# MusselBedHeater_RevG.net
KiCad netlist of a schematic drawn in EAGLE
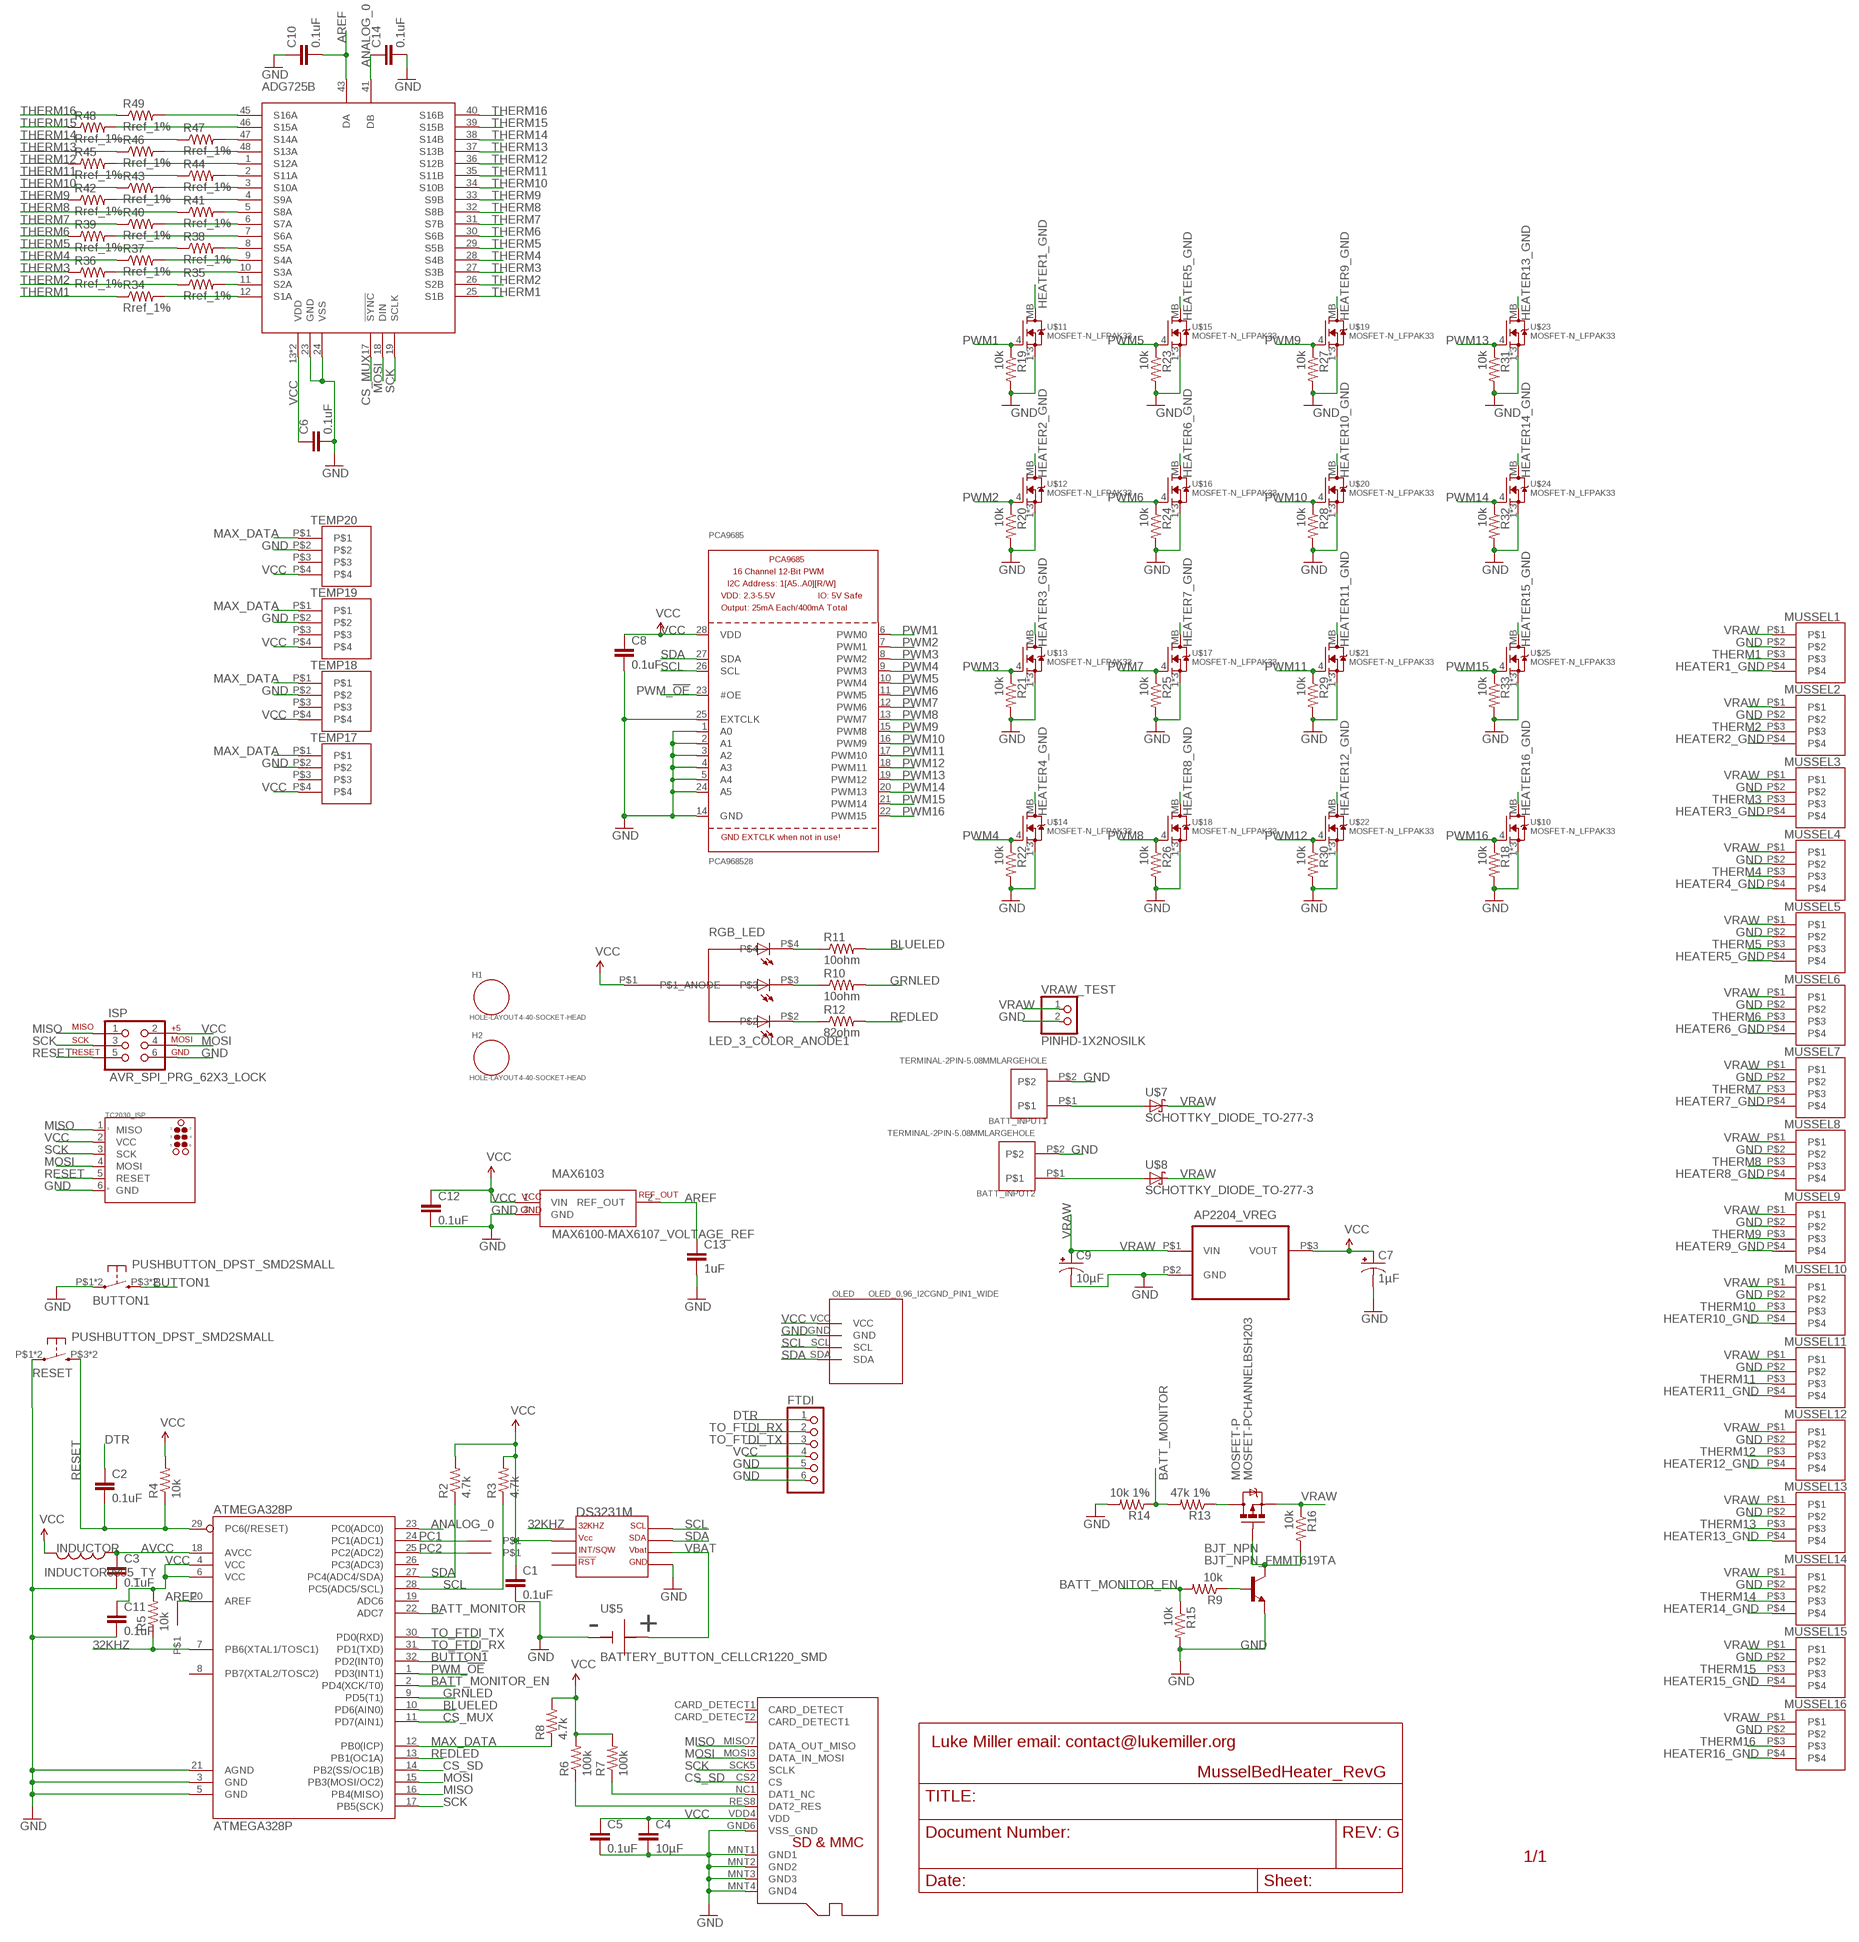
[diagram p0: schematic, sheet 1]

(export (version "E")
  (design (tool "Eeschema 10.0.6"))
  (components
    (comp (ref "ADG725B")
      (value "ADG725_MUX")
      (footprint "eagle-import:TQFP48")
      (libsource (lib "eagle-import") (part "ADG725_MUX"))
    )
    (comp (ref "AP2204_VREG")
      (value "AP2204R")
      (footprint "eagle-import:SOT-89")
      (libsource (lib "eagle-import") (part "AP2204R"))
    )
    (comp (ref "AREF")
      (value "PINHD-1X1STANDARD")
      (footprint "eagle-import:1X01")
      (libsource (lib "eagle-import") (part "PINHD-1X1STANDARD"))
    )
    (comp (ref "ATMEGA328P")
      (value "ATMEGA328P")
      (footprint "eagle-import:TQFP32-08")
      (libsource (lib "eagle-import") (part "ATMEGA328_SMT"))
    )
    (comp (ref "BATT_INPUT1")
      (value "TERMINAL-2PIN-5.08MMLARGEHOLE")
      (footprint "eagle-import:TERMINAL-2PIN-5.08MM_LARGEHOLE")
      (libsource (lib "eagle-import") (part "TERMINAL-2PIN-5.08MMLARGEHOLE"))
    )
    (comp (ref "BATT_INPUT2")
      (value "TERMINAL-2PIN-5.08MMLARGEHOLE")
      (footprint "eagle-import:TERMINAL-2PIN-5.08MM_LARGEHOLE")
      (libsource (lib "eagle-import") (part "TERMINAL-2PIN-5.08MMLARGEHOLE"))
    )
    (comp (ref "BJT_NPN")
      (value "BJT_NPN_FMMT619TA")
      (footprint "eagle-import:SOT23")
      (libsource (lib "eagle-import") (part "BJT_NPN_FMMT619TA"))
    )
    (comp (ref "BUTTON1")
      (value "PUSHBUTTON_DPST_SMD2SMALL")
      (footprint "eagle-import:PUSHBUTTON_SPST_PTS525_SERIES")
      (libsource (lib "eagle-import") (part "PUSHBUTTON_DPST_SMD2SMALL"))
    )
    (comp (ref "C1")
      (value "0.1uF")
      (footprint "eagle-import:0603")
      (libsource (lib "eagle-import") (part "CAP0603"))
    )
    (comp (ref "C2")
      (value "0.1uF")
      (footprint "eagle-import:0603")
      (libsource (lib "eagle-import") (part "CAP0603"))
    )
    (comp (ref "C3")
      (value "0.1uF")
      (footprint "eagle-import:0603")
      (libsource (lib "eagle-import") (part "CAP0603"))
    )
    (comp (ref "C4")
      (value "10µF")
      (footprint "eagle-import:0603")
      (libsource (lib "eagle-import") (part "CAP0603"))
    )
    (comp (ref "C5")
      (value "0.1uF")
      (footprint "eagle-import:0603")
      (libsource (lib "eagle-import") (part "CAP0603"))
    )
    (comp (ref "C6")
      (value "0.1uF")
      (footprint "eagle-import:0603")
      (libsource (lib "eagle-import") (part "CAP0603"))
    )
    (comp (ref "C7")
      (value "1µF")
      (footprint "eagle-import:PANASONIC_B")
      (libsource (lib "eagle-import") (part "CPOL-USB"))
    )
    (comp (ref "C8")
      (value "0.1uF")
      (footprint "eagle-import:0603")
      (libsource (lib "eagle-import") (part "CAP0603"))
    )
    (comp (ref "C9")
      (value "10µF")
      (footprint "eagle-import:PANASONIC_C")
      (libsource (lib "eagle-import") (part "CPOL-USC"))
    )
    (comp (ref "C10")
      (value "0.1uF")
      (footprint "eagle-import:0603")
      (libsource (lib "eagle-import") (part "CAP0603"))
    )
    (comp (ref "C11")
      (value "0.1uF")
      (footprint "eagle-import:0603")
      (libsource (lib "eagle-import") (part "CAP0603"))
    )
    (comp (ref "C12")
      (value "0.1uF")
      (footprint "eagle-import:0603")
      (libsource (lib "eagle-import") (part "CAP0603"))
    )
    (comp (ref "C13")
      (value "1uF")
      (footprint "eagle-import:0603")
      (libsource (lib "eagle-import") (part "CAP0603"))
    )
    (comp (ref "C14")
      (value "0.1uF")
      (footprint "eagle-import:0603")
      (libsource (lib "eagle-import") (part "CAP0603"))
    )
    (comp (ref "DS3231M")
      (value "DS3231MSOIC-8")
      (footprint "eagle-import:DS3231M_SOIC8")
      (libsource (lib "eagle-import") (part "DS3231MSOIC-8"))
    )
    (comp (ref "FTDI")
      (value "PINHD-1X6RA")
      (footprint "eagle-import:1X06-RIGHT_ANGLE")
      (libsource (lib "eagle-import") (part "PINHD-1X6RA"))
    )
    (comp (ref "H1")
      (value "HOLE-LAYOUT4-40-SOCKET-HEAD")
      (footprint "eagle-import:4-40-SCREW-HOLE")
      (libsource (lib "eagle-import") (part "HOLE-LAYOUT4-40-SOCKET-HEAD"))
    )
    (comp (ref "H2")
      (value "HOLE-LAYOUT4-40-SOCKET-HEAD")
      (footprint "eagle-import:4-40-SCREW-HOLE")
      (libsource (lib "eagle-import") (part "HOLE-LAYOUT4-40-SOCKET-HEAD"))
    )
    (comp (ref "INDUCTOR")
      (value "INDUCTOR0805_TY")
      (footprint "eagle-import:I_0805")
      (libsource (lib "eagle-import") (part "INDUCTOR0805_TY"))
    )
    (comp (ref "ISP")
      (value "AVR_SPI_PRG_62X3_LOCK")
      (footprint "eagle-import:2X3_LOCK")
      (libsource (lib "eagle-import") (part "AVR_SPI_PRG_62X3_LOCK"))
    )
    (comp (ref "MAX6103")
      (value "MAX6100-MAX6107_VOLTAGE_REF")
      (footprint "eagle-import:SOT23-3")
      (libsource (lib "eagle-import") (part "MAX6100-MAX6107_VOLTAGE_REF"))
    )
    (comp (ref "MOSFET-P")
      (value "MOSFET-PCHANNELBSH203")
      (footprint "eagle-import:SOT23-3")
      (libsource (lib "eagle-import") (part "MOSFET-PCHANNELBSH203"))
    )
    (comp (ref "MUSSEL1")
      (value "MOLEX_KK_254_4_PIN_HEADER")
      (footprint "eagle-import:MOLEX_KK_254_4PIN_HEADER")
      (libsource (lib "eagle-import") (part "MOLEX_KK_254_4_PIN_HEADER"))
    )
    (comp (ref "MUSSEL2")
      (value "MOLEX_KK_254_4_PIN_HEADER")
      (footprint "eagle-import:MOLEX_KK_254_4PIN_HEADER")
      (libsource (lib "eagle-import") (part "MOLEX_KK_254_4_PIN_HEADER"))
    )
    (comp (ref "MUSSEL3")
      (value "MOLEX_KK_254_4_PIN_HEADER")
      (footprint "eagle-import:MOLEX_KK_254_4PIN_HEADER")
      (libsource (lib "eagle-import") (part "MOLEX_KK_254_4_PIN_HEADER"))
    )
    (comp (ref "MUSSEL4")
      (value "MOLEX_KK_254_4_PIN_HEADER")
      (footprint "eagle-import:MOLEX_KK_254_4PIN_HEADER")
      (libsource (lib "eagle-import") (part "MOLEX_KK_254_4_PIN_HEADER"))
    )
    (comp (ref "MUSSEL5")
      (value "MOLEX_KK_254_4_PIN_HEADER")
      (footprint "eagle-import:MOLEX_KK_254_4PIN_HEADER")
      (libsource (lib "eagle-import") (part "MOLEX_KK_254_4_PIN_HEADER"))
    )
    (comp (ref "MUSSEL6")
      (value "MOLEX_KK_254_4_PIN_HEADER")
      (footprint "eagle-import:MOLEX_KK_254_4PIN_HEADER")
      (libsource (lib "eagle-import") (part "MOLEX_KK_254_4_PIN_HEADER"))
    )
    (comp (ref "MUSSEL7")
      (value "MOLEX_KK_254_4_PIN_HEADER")
      (footprint "eagle-import:MOLEX_KK_254_4PIN_HEADER")
      (libsource (lib "eagle-import") (part "MOLEX_KK_254_4_PIN_HEADER"))
    )
    (comp (ref "MUSSEL8")
      (value "MOLEX_KK_254_4_PIN_HEADER")
      (footprint "eagle-import:MOLEX_KK_254_4PIN_HEADER")
      (libsource (lib "eagle-import") (part "MOLEX_KK_254_4_PIN_HEADER"))
    )
    (comp (ref "MUSSEL9")
      (value "MOLEX_KK_254_4_PIN_HEADER")
      (footprint "eagle-import:MOLEX_KK_254_4PIN_HEADER")
      (libsource (lib "eagle-import") (part "MOLEX_KK_254_4_PIN_HEADER"))
    )
    (comp (ref "MUSSEL10")
      (value "MOLEX_KK_254_4_PIN_HEADER")
      (footprint "eagle-import:MOLEX_KK_254_4PIN_HEADER")
      (libsource (lib "eagle-import") (part "MOLEX_KK_254_4_PIN_HEADER"))
    )
    (comp (ref "MUSSEL11")
      (value "MOLEX_KK_254_4_PIN_HEADER")
      (footprint "eagle-import:MOLEX_KK_254_4PIN_HEADER")
      (libsource (lib "eagle-import") (part "MOLEX_KK_254_4_PIN_HEADER"))
    )
    (comp (ref "MUSSEL12")
      (value "MOLEX_KK_254_4_PIN_HEADER")
      (footprint "eagle-import:MOLEX_KK_254_4PIN_HEADER")
      (libsource (lib "eagle-import") (part "MOLEX_KK_254_4_PIN_HEADER"))
    )
    (comp (ref "MUSSEL13")
      (value "MOLEX_KK_254_4_PIN_HEADER")
      (footprint "eagle-import:MOLEX_KK_254_4PIN_HEADER")
      (libsource (lib "eagle-import") (part "MOLEX_KK_254_4_PIN_HEADER"))
    )
    (comp (ref "MUSSEL14")
      (value "MOLEX_KK_254_4_PIN_HEADER")
      (footprint "eagle-import:MOLEX_KK_254_4PIN_HEADER")
      (libsource (lib "eagle-import") (part "MOLEX_KK_254_4_PIN_HEADER"))
    )
    (comp (ref "MUSSEL15")
      (value "MOLEX_KK_254_4_PIN_HEADER")
      (footprint "eagle-import:MOLEX_KK_254_4PIN_HEADER")
      (libsource (lib "eagle-import") (part "MOLEX_KK_254_4_PIN_HEADER"))
    )
    (comp (ref "MUSSEL16")
      (value "MOLEX_KK_254_4_PIN_HEADER")
      (footprint "eagle-import:MOLEX_KK_254_4PIN_HEADER")
      (libsource (lib "eagle-import") (part "MOLEX_KK_254_4_PIN_HEADER"))
    )
    (comp (ref "OLED")
      (value "OLED_0.96_I2CGND_PIN1_WIDE")
      (footprint "eagle-import:OLED_0.96_I2C_GND_PIN1_WIDE")
      (libsource (lib "eagle-import") (part "OLED_0.96_I2CGND_PIN1_WIDE"))
    )
    (comp (ref "PC1")
      (value "PINHD-1X1STANDARD")
      (footprint "eagle-import:1X01")
      (libsource (lib "eagle-import") (part "PINHD-1X1STANDARD"))
    )
    (comp (ref "PC2")
      (value "PINHD-1X1STANDARD")
      (footprint "eagle-import:1X01")
      (libsource (lib "eagle-import") (part "PINHD-1X1STANDARD"))
    )
    (comp (ref "PCA9685")
      (value "PCA968528")
      (footprint "eagle-import:28-TSSOP")
      (libsource (lib "eagle-import") (part "PCA968528"))
    )
    (comp (ref "R2")
      (value "4.7k")
      (footprint "eagle-import:R0603")
      (libsource (lib "eagle-import") (part "RESISTOR_SMDR0603"))
    )
    (comp (ref "R3")
      (value "4.7k")
      (footprint "eagle-import:R0603")
      (libsource (lib "eagle-import") (part "RESISTOR_SMDR0603"))
    )
    (comp (ref "R4")
      (value "10k")
      (footprint "eagle-import:R0603")
      (libsource (lib "eagle-import") (part "RESISTOR_SMDR0603"))
    )
    (comp (ref "R5")
      (value "10k")
      (footprint "eagle-import:R0603")
      (libsource (lib "eagle-import") (part "RESISTOR_SMDR0603"))
    )
    (comp (ref "R6")
      (value "100k")
      (footprint "eagle-import:R0603")
      (libsource (lib "eagle-import") (part "RESISTOR_SMDR0603"))
    )
    (comp (ref "R7")
      (value "100k")
      (footprint "eagle-import:R0603")
      (libsource (lib "eagle-import") (part "RESISTOR_SMDR0603"))
    )
    (comp (ref "R8")
      (value "4.7k")
      (footprint "eagle-import:R0603")
      (libsource (lib "eagle-import") (part "RESISTOR_SMDR0603"))
    )
    (comp (ref "R9")
      (value "10k")
      (footprint "eagle-import:R0603")
      (libsource (lib "eagle-import") (part "RESISTOR_SMDR0603"))
    )
    (comp (ref "R10")
      (value "10ohm")
      (footprint "eagle-import:R0603")
      (libsource (lib "eagle-import") (part "RESISTOR_SMDR0603"))
    )
    (comp (ref "R11")
      (value "10ohm")
      (footprint "eagle-import:R0603")
      (libsource (lib "eagle-import") (part "RESISTOR_SMDR0603"))
    )
    (comp (ref "R12")
      (value "82ohm")
      (footprint "eagle-import:R0603")
      (libsource (lib "eagle-import") (part "RESISTOR_SMDR0603"))
    )
    (comp (ref "R13")
      (value "47k 1%")
      (footprint "eagle-import:R0603")
      (libsource (lib "eagle-import") (part "RESISTOR_SMDR0603"))
    )
    (comp (ref "R14")
      (value "10k 1%")
      (footprint "eagle-import:R0603")
      (libsource (lib "eagle-import") (part "RESISTOR_SMDR0603"))
    )
    (comp (ref "R15")
      (value "10k")
      (footprint "eagle-import:R0603")
      (libsource (lib "eagle-import") (part "RESISTOR_SMDR0603"))
    )
    (comp (ref "R16")
      (value "10k")
      (footprint "eagle-import:R0603")
      (libsource (lib "eagle-import") (part "RESISTOR_SMDR0603"))
    )
    (comp (ref "R18")
      (value "10k")
      (footprint "eagle-import:R0603")
      (libsource (lib "eagle-import") (part "RESISTOR_SMDR0603"))
    )
    (comp (ref "R19")
      (value "10k")
      (footprint "eagle-import:R0603")
      (libsource (lib "eagle-import") (part "RESISTOR_SMDR0603"))
    )
    (comp (ref "R20")
      (value "10k")
      (footprint "eagle-import:R0603")
      (libsource (lib "eagle-import") (part "RESISTOR_SMDR0603"))
    )
    (comp (ref "R21")
      (value "10k")
      (footprint "eagle-import:R0603")
      (libsource (lib "eagle-import") (part "RESISTOR_SMDR0603"))
    )
    (comp (ref "R22")
      (value "10k")
      (footprint "eagle-import:R0603")
      (libsource (lib "eagle-import") (part "RESISTOR_SMDR0603"))
    )
    (comp (ref "R23")
      (value "10k")
      (footprint "eagle-import:R0603")
      (libsource (lib "eagle-import") (part "RESISTOR_SMDR0603"))
    )
    (comp (ref "R24")
      (value "10k")
      (footprint "eagle-import:R0603")
      (libsource (lib "eagle-import") (part "RESISTOR_SMDR0603"))
    )
    (comp (ref "R25")
      (value "10k")
      (footprint "eagle-import:R0603")
      (libsource (lib "eagle-import") (part "RESISTOR_SMDR0603"))
    )
    (comp (ref "R26")
      (value "10k")
      (footprint "eagle-import:R0603")
      (libsource (lib "eagle-import") (part "RESISTOR_SMDR0603"))
    )
    (comp (ref "R27")
      (value "10k")
      (footprint "eagle-import:R0603")
      (libsource (lib "eagle-import") (part "RESISTOR_SMDR0603"))
    )
    (comp (ref "R28")
      (value "10k")
      (footprint "eagle-import:R0603")
      (libsource (lib "eagle-import") (part "RESISTOR_SMDR0603"))
    )
    (comp (ref "R29")
      (value "10k")
      (footprint "eagle-import:R0603")
      (libsource (lib "eagle-import") (part "RESISTOR_SMDR0603"))
    )
    (comp (ref "R30")
      (value "10k")
      (footprint "eagle-import:R0603")
      (libsource (lib "eagle-import") (part "RESISTOR_SMDR0603"))
    )
    (comp (ref "R31")
      (value "10k")
      (footprint "eagle-import:R0603")
      (libsource (lib "eagle-import") (part "RESISTOR_SMDR0603"))
    )
    (comp (ref "R32")
      (value "10k")
      (footprint "eagle-import:R0603")
      (libsource (lib "eagle-import") (part "RESISTOR_SMDR0603"))
    )
    (comp (ref "R33")
      (value "10k")
      (footprint "eagle-import:R0603")
      (libsource (lib "eagle-import") (part "RESISTOR_SMDR0603"))
    )
    (comp (ref "R34")
      (value "Rref_1%")
      (footprint "eagle-import:R0603")
      (libsource (lib "eagle-import") (part "RESISTOR_SMDR0603"))
    )
    (comp (ref "R35")
      (value "Rref_1%")
      (footprint "eagle-import:R0603")
      (libsource (lib "eagle-import") (part "RESISTOR_SMDR0603"))
    )
    (comp (ref "R36")
      (value "Rref_1%")
      (footprint "eagle-import:R0603")
      (libsource (lib "eagle-import") (part "RESISTOR_SMDR0603"))
    )
    (comp (ref "R37")
      (value "Rref_1%")
      (footprint "eagle-import:R0603")
      (libsource (lib "eagle-import") (part "RESISTOR_SMDR0603"))
    )
    (comp (ref "R38")
      (value "Rref_1%")
      (footprint "eagle-import:R0603")
      (libsource (lib "eagle-import") (part "RESISTOR_SMDR0603"))
    )
    (comp (ref "R39")
      (value "Rref_1%")
      (footprint "eagle-import:R0603")
      (libsource (lib "eagle-import") (part "RESISTOR_SMDR0603"))
    )
    (comp (ref "R40")
      (value "Rref_1%")
      (footprint "eagle-import:R0603")
      (libsource (lib "eagle-import") (part "RESISTOR_SMDR0603"))
    )
    (comp (ref "R41")
      (value "Rref_1%")
      (footprint "eagle-import:R0603")
      (libsource (lib "eagle-import") (part "RESISTOR_SMDR0603"))
    )
    (comp (ref "R42")
      (value "Rref_1%")
      (footprint "eagle-import:R0603")
      (libsource (lib "eagle-import") (part "RESISTOR_SMDR0603"))
    )
    (comp (ref "R43")
      (value "Rref_1%")
      (footprint "eagle-import:R0603")
      (libsource (lib "eagle-import") (part "RESISTOR_SMDR0603"))
    )
    (comp (ref "R44")
      (value "Rref_1%")
      (footprint "eagle-import:R0603")
      (libsource (lib "eagle-import") (part "RESISTOR_SMDR0603"))
    )
    (comp (ref "R45")
      (value "Rref_1%")
      (footprint "eagle-import:R0603")
      (libsource (lib "eagle-import") (part "RESISTOR_SMDR0603"))
    )
    (comp (ref "R46")
      (value "Rref_1%")
      (footprint "eagle-import:R0603")
      (libsource (lib "eagle-import") (part "RESISTOR_SMDR0603"))
    )
    (comp (ref "R47")
      (value "Rref_1%")
      (footprint "eagle-import:R0603")
      (libsource (lib "eagle-import") (part "RESISTOR_SMDR0603"))
    )
    (comp (ref "R48")
      (value "Rref_1%")
      (footprint "eagle-import:R0603")
      (libsource (lib "eagle-import") (part "RESISTOR_SMDR0603"))
    )
    (comp (ref "R49")
      (value "Rref_1%")
      (footprint "eagle-import:R0603")
      (libsource (lib "eagle-import") (part "RESISTOR_SMDR0603"))
    )
    (comp (ref "RESET")
      (value "PUSHBUTTON_DPST_SMD2SMALL")
      (footprint "eagle-import:PUSHBUTTON_SPST_PTS525_SERIES")
      (libsource (lib "eagle-import") (part "PUSHBUTTON_DPST_SMD2SMALL"))
    )
    (comp (ref "RGB_LED")
      (value "LED_3_COLOR_ANODE1")
      (footprint "eagle-import:LED_RGB_SMD_1.6X1.6")
      (libsource (lib "eagle-import") (part "LED_3_COLOR_ANODE1"))
    )
    (comp (ref "TC2030_ISP")
      (value "TC2030-MCP-NL")
      (footprint "eagle-import:TC2030-MCP-NL")
      (libsource (lib "eagle-import") (part "TC2030-MCP-NL"))
    )
    (comp (ref "TEMP17")
      (value "MOLEX_KK_254_4_PIN_HEADER")
      (footprint "eagle-import:MOLEX_KK_254_4PIN_HEADER")
      (libsource (lib "eagle-import") (part "MOLEX_KK_254_4_PIN_HEADER"))
    )
    (comp (ref "TEMP18")
      (value "MOLEX_KK_254_4_PIN_HEADER")
      (footprint "eagle-import:MOLEX_KK_254_4PIN_HEADER")
      (libsource (lib "eagle-import") (part "MOLEX_KK_254_4_PIN_HEADER"))
    )
    (comp (ref "TEMP19")
      (value "MOLEX_KK_254_4_PIN_HEADER")
      (footprint "eagle-import:MOLEX_KK_254_4PIN_HEADER")
      (libsource (lib "eagle-import") (part "MOLEX_KK_254_4_PIN_HEADER"))
    )
    (comp (ref "TEMP20")
      (value "MOLEX_KK_254_4_PIN_HEADER")
      (footprint "eagle-import:MOLEX_KK_254_4PIN_HEADER")
      (libsource (lib "eagle-import") (part "MOLEX_KK_254_4_PIN_HEADER"))
    )
    (comp (ref "U$2")
      (value "MICROSD_MOLEX_REVERSECURRENT")
      (footprint "eagle-import:MICROSD_SOCKET_MOLEX_REVERSEMOUNT")
      (libsource (lib "eagle-import") (part "MICROSD_MOLEX_REVERSECURRENT"))
    )
    (comp (ref "U$5")
      (value "BATTERY_BUTTON_CELLCR1220_SMD")
      (footprint "eagle-import:CR1220_BATTERY_HOLDER_SMD")
      (libsource (lib "eagle-import") (part "BATTERY_BUTTON_CELLCR1220_SMD"))
    )
    (comp (ref "U$7")
      (value "SCHOTTKY_DIODE_TO-277-3")
      (footprint "eagle-import:TO-277-3")
      (libsource (lib "eagle-import") (part "SCHOTTKY_DIODE_TO-277-3"))
    )
    (comp (ref "U$8")
      (value "SCHOTTKY_DIODE_TO-277-3")
      (footprint "eagle-import:TO-277-3")
      (libsource (lib "eagle-import") (part "SCHOTTKY_DIODE_TO-277-3"))
    )
    (comp (ref "U$10")
      (value "MOSFET-N_LFPAK33")
      (footprint "eagle-import:SOT1210")
      (libsource (lib "eagle-import") (part "MOSFET-N_LFPAK33"))
    )
    (comp (ref "U$11")
      (value "MOSFET-N_LFPAK33")
      (footprint "eagle-import:SOT1210")
      (libsource (lib "eagle-import") (part "MOSFET-N_LFPAK33"))
    )
    (comp (ref "U$12")
      (value "MOSFET-N_LFPAK33")
      (footprint "eagle-import:SOT1210")
      (libsource (lib "eagle-import") (part "MOSFET-N_LFPAK33"))
    )
    (comp (ref "U$13")
      (value "MOSFET-N_LFPAK33")
      (footprint "eagle-import:SOT1210")
      (libsource (lib "eagle-import") (part "MOSFET-N_LFPAK33"))
    )
    (comp (ref "U$14")
      (value "MOSFET-N_LFPAK33")
      (footprint "eagle-import:SOT1210")
      (libsource (lib "eagle-import") (part "MOSFET-N_LFPAK33"))
    )
    (comp (ref "U$15")
      (value "MOSFET-N_LFPAK33")
      (footprint "eagle-import:SOT1210")
      (libsource (lib "eagle-import") (part "MOSFET-N_LFPAK33"))
    )
    (comp (ref "U$16")
      (value "MOSFET-N_LFPAK33")
      (footprint "eagle-import:SOT1210")
      (libsource (lib "eagle-import") (part "MOSFET-N_LFPAK33"))
    )
    (comp (ref "U$17")
      (value "MOSFET-N_LFPAK33")
      (footprint "eagle-import:SOT1210")
      (libsource (lib "eagle-import") (part "MOSFET-N_LFPAK33"))
    )
    (comp (ref "U$18")
      (value "MOSFET-N_LFPAK33")
      (footprint "eagle-import:SOT1210")
      (libsource (lib "eagle-import") (part "MOSFET-N_LFPAK33"))
    )
    (comp (ref "U$19")
      (value "MOSFET-N_LFPAK33")
      (footprint "eagle-import:SOT1210")
      (libsource (lib "eagle-import") (part "MOSFET-N_LFPAK33"))
    )
    (comp (ref "U$20")
      (value "MOSFET-N_LFPAK33")
      (footprint "eagle-import:SOT1210")
      (libsource (lib "eagle-import") (part "MOSFET-N_LFPAK33"))
    )
    (comp (ref "U$21")
      (value "MOSFET-N_LFPAK33")
      (footprint "eagle-import:SOT1210")
      (libsource (lib "eagle-import") (part "MOSFET-N_LFPAK33"))
    )
    (comp (ref "U$22")
      (value "MOSFET-N_LFPAK33")
      (footprint "eagle-import:SOT1210")
      (libsource (lib "eagle-import") (part "MOSFET-N_LFPAK33"))
    )
    (comp (ref "U$23")
      (value "MOSFET-N_LFPAK33")
      (footprint "eagle-import:SOT1210")
      (libsource (lib "eagle-import") (part "MOSFET-N_LFPAK33"))
    )
    (comp (ref "U$24")
      (value "MOSFET-N_LFPAK33")
      (footprint "eagle-import:SOT1210")
      (libsource (lib "eagle-import") (part "MOSFET-N_LFPAK33"))
    )
    (comp (ref "U$25")
      (value "MOSFET-N_LFPAK33")
      (footprint "eagle-import:SOT1210")
      (libsource (lib "eagle-import") (part "MOSFET-N_LFPAK33"))
    )
    (comp (ref "VRAW_TEST")
      (value "PINHD-1X2NOSILK")
      (footprint "eagle-import:1X02_NOSILK")
      (libsource (lib "eagle-import") (part "PINHD-1X2NOSILK"))
    )
  )
  (nets
    (net (code "1") (name "/32KHZ") (class "Default")
      (node (ref "ATMEGA328P") (pin "7") (pinfunction "PB6(XTAL1/TOSC1)_7") (pintype "bidirectional"))
      (node (ref "DS3231M") (pin "1") (pinfunction "P$1_32KHZ_1") (pintype "bidirectional"))
      (node (ref "R5") (pin "1") (pinfunction "1_1") (pintype "passive"))
    )
    (net (code "2") (name "/ANALOG_0") (class "Default")
      (node (ref "ADG725B") (pin "41") (pinfunction "DB_41") (pintype "bidirectional"))
      (node (ref "ATMEGA328P") (pin "23") (pinfunction "PC0(ADC0)_23") (pintype "bidirectional"))
      (node (ref "C14") (pin "1") (pinfunction "1_1") (pintype "passive"))
    )
    (net (code "3") (name "/AREF") (class "Default")
      (node (ref "ADG725B") (pin "43") (pinfunction "DA_43") (pintype "bidirectional"))
      (node (ref "AREF") (pin "1") (pinfunction "P$1_1") (pintype "bidirectional"))
      (node (ref "ATMEGA328P") (pin "20") (pinfunction "AREF_20") (pintype "bidirectional"))
      (node (ref "C10") (pin "2") (pinfunction "2_2") (pintype "passive"))
      (node (ref "C13") (pin "1") (pinfunction "1_1") (pintype "passive"))
      (node (ref "MAX6103") (pin "2") (pinfunction "REF_OUT_2") (pintype "bidirectional"))
    )
    (net (code "4") (name "/AVCC") (class "Default")
      (node (ref "ATMEGA328P") (pin "18") (pinfunction "AVCC_18") (pintype "bidirectional"))
      (node (ref "C3") (pin "1") (pinfunction "1_1") (pintype "passive"))
      (node (ref "INDUCTOR") (pin "P$1") (pinfunction "1_P$1") (pintype "passive"))
    )
    (net (code "5") (name "/BATT_MONITOR") (class "Default")
      (node (ref "ATMEGA328P") (pin "22") (pinfunction "ADC7_22") (pintype "bidirectional"))
      (node (ref "R13") (pin "2") (pinfunction "2_2") (pintype "passive"))
      (node (ref "R14") (pin "1") (pinfunction "1_1") (pintype "passive"))
    )
    (net (code "6") (name "/BATT_MONITOR_EN") (class "Default")
      (node (ref "ATMEGA328P") (pin "2") (pinfunction "PD4(XCK/T0)_2") (pintype "bidirectional"))
      (node (ref "R15") (pin "1") (pinfunction "1_1") (pintype "passive"))
      (node (ref "R9") (pin "2") (pinfunction "2_2") (pintype "passive"))
    )
    (net (code "7") (name "/BLUELED") (class "Default")
      (node (ref "ATMEGA328P") (pin "10") (pinfunction "PD6(AIN0)_10") (pintype "bidirectional"))
      (node (ref "R11") (pin "2") (pinfunction "2_2") (pintype "passive"))
    )
    (net (code "8") (name "/BUTTON1") (class "Default")
      (node (ref "ATMEGA328P") (pin "32") (pinfunction "PD2(INT0)_32") (pintype "bidirectional"))
      (node (ref "BUTTON1") (pin "P$3") (pinfunction "S_P$3") (pintype "passive"))
      (node (ref "BUTTON1") (pin "P$4") (pinfunction "S_P$4") (pintype "passive"))
    )
    (net (code "9") (name "/CS_MUX") (class "Default")
      (node (ref "ADG725B") (pin "17") (pinfunction "~{SYNC}_17") (pintype "bidirectional"))
      (node (ref "ATMEGA328P") (pin "11") (pinfunction "PD7(AIN1)_11") (pintype "bidirectional"))
    )
    (net (code "10") (name "/CS_SD") (class "Default")
      (node (ref "ATMEGA328P") (pin "14") (pinfunction "PB2(SS/OC1B)_14") (pintype "bidirectional"))
      (node (ref "U$2") (pin "CS2") (pinfunction "CS_CS2") (pintype "input"))
    )
    (net (code "11") (name "/DTR") (class "Default")
      (node (ref "C2") (pin "1") (pinfunction "1_1") (pintype "passive"))
      (node (ref "FTDI") (pin "1") (pinfunction "1_1") (pintype "passive"))
    )
    (net (code "12") (name "/GRNLED") (class "Default")
      (node (ref "ATMEGA328P") (pin "9") (pinfunction "PD5(T1)_9") (pintype "bidirectional"))
      (node (ref "R10") (pin "2") (pinfunction "2_2") (pintype "passive"))
    )
    (net (code "13") (name "/HEATER1_GND") (class "Default")
      (node (ref "MUSSEL1") (pin "P$4") (pinfunction "P$4_P$4") (pintype "bidirectional"))
      (node (ref "U$11") (pin "MB") (pinfunction "D_MB") (pintype "bidirectional"))
    )
    (net (code "14") (name "/HEATER2_GND") (class "Default")
      (node (ref "MUSSEL2") (pin "P$4") (pinfunction "P$4_P$4") (pintype "bidirectional"))
      (node (ref "U$12") (pin "MB") (pinfunction "D_MB") (pintype "bidirectional"))
    )
    (net (code "15") (name "/HEATER3_GND") (class "Default")
      (node (ref "MUSSEL3") (pin "P$4") (pinfunction "P$4_P$4") (pintype "bidirectional"))
      (node (ref "U$13") (pin "MB") (pinfunction "D_MB") (pintype "bidirectional"))
    )
    (net (code "16") (name "/HEATER4_GND") (class "Default")
      (node (ref "MUSSEL4") (pin "P$4") (pinfunction "P$4_P$4") (pintype "bidirectional"))
      (node (ref "U$14") (pin "MB") (pinfunction "D_MB") (pintype "bidirectional"))
    )
    (net (code "17") (name "/HEATER5_GND") (class "Default")
      (node (ref "MUSSEL5") (pin "P$4") (pinfunction "P$4_P$4") (pintype "bidirectional"))
      (node (ref "U$15") (pin "MB") (pinfunction "D_MB") (pintype "bidirectional"))
    )
    (net (code "18") (name "/HEATER6_GND") (class "Default")
      (node (ref "MUSSEL6") (pin "P$4") (pinfunction "P$4_P$4") (pintype "bidirectional"))
      (node (ref "U$16") (pin "MB") (pinfunction "D_MB") (pintype "bidirectional"))
    )
    (net (code "19") (name "/HEATER7_GND") (class "Default")
      (node (ref "MUSSEL7") (pin "P$4") (pinfunction "P$4_P$4") (pintype "bidirectional"))
      (node (ref "U$17") (pin "MB") (pinfunction "D_MB") (pintype "bidirectional"))
    )
    (net (code "20") (name "/HEATER8_GND") (class "Default")
      (node (ref "MUSSEL8") (pin "P$4") (pinfunction "P$4_P$4") (pintype "bidirectional"))
      (node (ref "U$18") (pin "MB") (pinfunction "D_MB") (pintype "bidirectional"))
    )
    (net (code "21") (name "/HEATER9_GND") (class "Default")
      (node (ref "MUSSEL9") (pin "P$4") (pinfunction "P$4_P$4") (pintype "bidirectional"))
      (node (ref "U$19") (pin "MB") (pinfunction "D_MB") (pintype "bidirectional"))
    )
    (net (code "22") (name "/HEATER10_GND") (class "Default")
      (node (ref "MUSSEL10") (pin "P$4") (pinfunction "P$4_P$4") (pintype "bidirectional"))
      (node (ref "U$20") (pin "MB") (pinfunction "D_MB") (pintype "bidirectional"))
    )
    (net (code "23") (name "/HEATER11_GND") (class "Default")
      (node (ref "MUSSEL11") (pin "P$4") (pinfunction "P$4_P$4") (pintype "bidirectional"))
      (node (ref "U$21") (pin "MB") (pinfunction "D_MB") (pintype "bidirectional"))
    )
    (net (code "24") (name "/HEATER12_GND") (class "Default")
      (node (ref "MUSSEL12") (pin "P$4") (pinfunction "P$4_P$4") (pintype "bidirectional"))
      (node (ref "U$22") (pin "MB") (pinfunction "D_MB") (pintype "bidirectional"))
    )
    (net (code "25") (name "/HEATER13_GND") (class "Default")
      (node (ref "MUSSEL13") (pin "P$4") (pinfunction "P$4_P$4") (pintype "bidirectional"))
      (node (ref "U$23") (pin "MB") (pinfunction "D_MB") (pintype "bidirectional"))
    )
    (net (code "26") (name "/HEATER14_GND") (class "Default")
      (node (ref "MUSSEL14") (pin "P$4") (pinfunction "P$4_P$4") (pintype "bidirectional"))
      (node (ref "U$24") (pin "MB") (pinfunction "D_MB") (pintype "bidirectional"))
    )
    (net (code "27") (name "/HEATER15_GND") (class "Default")
      (node (ref "MUSSEL15") (pin "P$4") (pinfunction "P$4_P$4") (pintype "bidirectional"))
      (node (ref "U$25") (pin "MB") (pinfunction "D_MB") (pintype "bidirectional"))
    )
    (net (code "28") (name "/HEATER16_GND") (class "Default")
      (node (ref "MUSSEL16") (pin "P$4") (pinfunction "P$4_P$4") (pintype "bidirectional"))
      (node (ref "U$10") (pin "MB") (pinfunction "D_MB") (pintype "bidirectional"))
    )
    (net (code "29") (name "/MAX_DATA") (class "Default")
      (node (ref "ATMEGA328P") (pin "12") (pinfunction "PB0(ICP)_12") (pintype "bidirectional"))
      (node (ref "R8") (pin "1") (pinfunction "1_1") (pintype "passive"))
      (node (ref "TEMP17") (pin "P$1") (pinfunction "P$1_P$1") (pintype "bidirectional"))
      (node (ref "TEMP18") (pin "P$1") (pinfunction "P$1_P$1") (pintype "bidirectional"))
      (node (ref "TEMP19") (pin "P$1") (pinfunction "P$1_P$1") (pintype "bidirectional"))
      (node (ref "TEMP20") (pin "P$1") (pinfunction "P$1_P$1") (pintype "bidirectional"))
    )
    (net (code "30") (name "/MISO") (class "Default")
      (node (ref "ATMEGA328P") (pin "16") (pinfunction "PB4(MISO)_16") (pintype "bidirectional"))
      (node (ref "ISP") (pin "1") (pinfunction "1_1") (pintype "passive"))
      (node (ref "TC2030_ISP") (pin "1") (pinfunction "MISO_1") (pintype "bidirectional"))
      (node (ref "U$2") (pin "MISO7") (pinfunction "DATA_OUT_MISO_MISO7") (pintype "output"))
    )
    (net (code "31") (name "/MOSI") (class "Default")
      (node (ref "ADG725B") (pin "18") (pinfunction "DIN_18") (pintype "bidirectional"))
      (node (ref "ATMEGA328P") (pin "15") (pinfunction "PB3(MOSI/OC2)_15") (pintype "bidirectional"))
      (node (ref "ISP") (pin "4") (pinfunction "4_4") (pintype "passive"))
      (node (ref "TC2030_ISP") (pin "4") (pinfunction "MOSI_4") (pintype "bidirectional"))
      (node (ref "U$2") (pin "MOSI3") (pinfunction "DATA_IN_MOSI_MOSI3") (pintype "input"))
    )
    (net (code "32") (name "/PC1") (class "Default")
      (node (ref "ATMEGA328P") (pin "24") (pinfunction "PC1(ADC1)_24") (pintype "bidirectional"))
      (node (ref "PC1") (pin "1") (pinfunction "P$1_1") (pintype "bidirectional"))
    )
    (net (code "33") (name "/PC2") (class "Default")
      (node (ref "ATMEGA328P") (pin "25") (pinfunction "PC2(ADC2)_25") (pintype "bidirectional"))
      (node (ref "PC2") (pin "1") (pinfunction "P$1_1") (pintype "bidirectional"))
    )
    (net (code "34") (name "/PWM1") (class "Default")
      (node (ref "PCA9685") (pin "6") (pinfunction "PWM0_6") (pintype "output"))
      (node (ref "R19") (pin "1") (pinfunction "1_1") (pintype "passive"))
      (node (ref "U$11") (pin "4") (pinfunction "G_4") (pintype "bidirectional"))
    )
    (net (code "35") (name "/PWM2") (class "Default")
      (node (ref "PCA9685") (pin "7") (pinfunction "PWM1_7") (pintype "output"))
      (node (ref "R20") (pin "1") (pinfunction "1_1") (pintype "passive"))
      (node (ref "U$12") (pin "4") (pinfunction "G_4") (pintype "bidirectional"))
    )
    (net (code "36") (name "/PWM3") (class "Default")
      (node (ref "PCA9685") (pin "8") (pinfunction "PWM2_8") (pintype "output"))
      (node (ref "R21") (pin "1") (pinfunction "1_1") (pintype "passive"))
      (node (ref "U$13") (pin "4") (pinfunction "G_4") (pintype "bidirectional"))
    )
    (net (code "37") (name "/PWM4") (class "Default")
      (node (ref "PCA9685") (pin "9") (pinfunction "PWM3_9") (pintype "output"))
      (node (ref "R22") (pin "1") (pinfunction "1_1") (pintype "passive"))
      (node (ref "U$14") (pin "4") (pinfunction "G_4") (pintype "bidirectional"))
    )
    (net (code "38") (name "/PWM5") (class "Default")
      (node (ref "PCA9685") (pin "10") (pinfunction "PWM4_10") (pintype "output"))
      (node (ref "R23") (pin "1") (pinfunction "1_1") (pintype "passive"))
      (node (ref "U$15") (pin "4") (pinfunction "G_4") (pintype "bidirectional"))
    )
    (net (code "39") (name "/PWM6") (class "Default")
      (node (ref "PCA9685") (pin "11") (pinfunction "PWM5_11") (pintype "output"))
      (node (ref "R24") (pin "1") (pinfunction "1_1") (pintype "passive"))
      (node (ref "U$16") (pin "4") (pinfunction "G_4") (pintype "bidirectional"))
    )
    (net (code "40") (name "/PWM7") (class "Default")
      (node (ref "PCA9685") (pin "12") (pinfunction "PWM6_12") (pintype "output"))
      (node (ref "R25") (pin "1") (pinfunction "1_1") (pintype "passive"))
      (node (ref "U$17") (pin "4") (pinfunction "G_4") (pintype "bidirectional"))
    )
    (net (code "41") (name "/PWM8") (class "Default")
      (node (ref "PCA9685") (pin "13") (pinfunction "PWM7_13") (pintype "output"))
      (node (ref "R26") (pin "1") (pinfunction "1_1") (pintype "passive"))
      (node (ref "U$18") (pin "4") (pinfunction "G_4") (pintype "bidirectional"))
    )
    (net (code "42") (name "/PWM9") (class "Default")
      (node (ref "PCA9685") (pin "15") (pinfunction "PWM8_15") (pintype "output"))
      (node (ref "R27") (pin "1") (pinfunction "1_1") (pintype "passive"))
      (node (ref "U$19") (pin "4") (pinfunction "G_4") (pintype "bidirectional"))
    )
    (net (code "43") (name "/PWM10") (class "Default")
      (node (ref "PCA9685") (pin "16") (pinfunction "PWM9_16") (pintype "output"))
      (node (ref "R28") (pin "1") (pinfunction "1_1") (pintype "passive"))
      (node (ref "U$20") (pin "4") (pinfunction "G_4") (pintype "bidirectional"))
    )
    (net (code "44") (name "/PWM11") (class "Default")
      (node (ref "PCA9685") (pin "17") (pinfunction "PWM10_17") (pintype "output"))
      (node (ref "R29") (pin "1") (pinfunction "1_1") (pintype "passive"))
      (node (ref "U$21") (pin "4") (pinfunction "G_4") (pintype "bidirectional"))
    )
    (net (code "45") (name "/PWM12") (class "Default")
      (node (ref "PCA9685") (pin "18") (pinfunction "PWM11_18") (pintype "output"))
      (node (ref "R30") (pin "1") (pinfunction "1_1") (pintype "passive"))
      (node (ref "U$22") (pin "4") (pinfunction "G_4") (pintype "bidirectional"))
    )
    (net (code "46") (name "/PWM13") (class "Default")
      (node (ref "PCA9685") (pin "19") (pinfunction "PWM12_19") (pintype "output"))
      (node (ref "R31") (pin "1") (pinfunction "1_1") (pintype "passive"))
      (node (ref "U$23") (pin "4") (pinfunction "G_4") (pintype "bidirectional"))
    )
    (net (code "47") (name "/PWM14") (class "Default")
      (node (ref "PCA9685") (pin "20") (pinfunction "PWM13_20") (pintype "output"))
      (node (ref "R32") (pin "1") (pinfunction "1_1") (pintype "passive"))
      (node (ref "U$24") (pin "4") (pinfunction "G_4") (pintype "bidirectional"))
    )
    (net (code "48") (name "/PWM15") (class "Default")
      (node (ref "PCA9685") (pin "21") (pinfunction "PWM14_21") (pintype "output"))
      (node (ref "R33") (pin "1") (pinfunction "1_1") (pintype "passive"))
      (node (ref "U$25") (pin "4") (pinfunction "G_4") (pintype "bidirectional"))
    )
    (net (code "49") (name "/PWM16") (class "Default")
      (node (ref "PCA9685") (pin "22") (pinfunction "PWM15_22") (pintype "output"))
      (node (ref "R18") (pin "1") (pinfunction "1_1") (pintype "passive"))
      (node (ref "U$10") (pin "4") (pinfunction "G_4") (pintype "bidirectional"))
    )
    (net (code "50") (name "/PWM_~{OE}") (class "Default")
      (node (ref "ATMEGA328P") (pin "1") (pinfunction "PD3(INT1)_1") (pintype "bidirectional"))
      (node (ref "PCA9685") (pin "23") (pinfunction "#OE_23") (pintype "input"))
    )
    (net (code "51") (name "/REDLED") (class "Default")
      (node (ref "ATMEGA328P") (pin "13") (pinfunction "PB1(OC1A)_13") (pintype "bidirectional"))
      (node (ref "R12") (pin "2") (pinfunction "2_2") (pintype "passive"))
    )
    (net (code "52") (name "/RESET") (class "Default")
      (node (ref "ATMEGA328P") (pin "29") (pinfunction "PC6(/RESET)_29") (pintype "bidirectional"))
      (node (ref "C2") (pin "2") (pinfunction "2_2") (pintype "passive"))
      (node (ref "ISP") (pin "5") (pinfunction "5_5") (pintype "passive"))
      (node (ref "R4") (pin "1") (pinfunction "1_1") (pintype "passive"))
      (node (ref "RESET") (pin "P$3") (pinfunction "S_P$3") (pintype "passive"))
      (node (ref "RESET") (pin "P$4") (pinfunction "S_P$4") (pintype "passive"))
      (node (ref "TC2030_ISP") (pin "5") (pinfunction "RESET_5") (pintype "bidirectional"))
    )
    (net (code "53") (name "/SCK") (class "Default")
      (node (ref "ADG725B") (pin "19") (pinfunction "SCLK_19") (pintype "bidirectional"))
      (node (ref "ATMEGA328P") (pin "17") (pinfunction "PB5(SCK)_17") (pintype "bidirectional"))
      (node (ref "ISP") (pin "3") (pinfunction "3_3") (pintype "passive"))
      (node (ref "TC2030_ISP") (pin "3") (pinfunction "SCK_3") (pintype "bidirectional"))
      (node (ref "U$2") (pin "SCK5") (pinfunction "SCLK_SCK5") (pintype "input"))
    )
    (net (code "54") (name "/SCL") (class "Default")
      (node (ref "ATMEGA328P") (pin "28") (pinfunction "PC5(ADC5/SCL)_28") (pintype "bidirectional"))
      (node (ref "DS3231M") (pin "8") (pinfunction "P$8_SCL_8") (pintype "bidirectional"))
      (node (ref "OLED") (pin "SCL") (pinfunction "SCL_SCL") (pintype "bidirectional"))
      (node (ref "PCA9685") (pin "26") (pinfunction "SCL_26") (pintype "bidirectional"))
      (node (ref "R3") (pin "1") (pinfunction "1_1") (pintype "passive"))
    )
    (net (code "55") (name "/SDA") (class "Default")
      (node (ref "ATMEGA328P") (pin "27") (pinfunction "PC4(ADC4/SDA)_27") (pintype "bidirectional"))
      (node (ref "DS3231M") (pin "7") (pinfunction "P$7_SDA_7") (pintype "bidirectional"))
      (node (ref "OLED") (pin "SDA") (pinfunction "SDA_SDA") (pintype "bidirectional"))
      (node (ref "PCA9685") (pin "27") (pinfunction "SDA_27") (pintype "bidirectional"))
      (node (ref "R2") (pin "1") (pinfunction "1_1") (pintype "passive"))
    )
    (net (code "56") (name "/THERM1") (class "Default")
      (node (ref "ADG725B") (pin "25") (pinfunction "S1B_25") (pintype "bidirectional"))
      (node (ref "MUSSEL1") (pin "P$3") (pinfunction "P$3_P$3") (pintype "bidirectional"))
      (node (ref "R34") (pin "1") (pinfunction "1_1") (pintype "passive"))
    )
    (net (code "57") (name "/THERM2") (class "Default")
      (node (ref "ADG725B") (pin "26") (pinfunction "S2B_26") (pintype "bidirectional"))
      (node (ref "MUSSEL2") (pin "P$3") (pinfunction "P$3_P$3") (pintype "bidirectional"))
      (node (ref "R35") (pin "1") (pinfunction "1_1") (pintype "passive"))
    )
    (net (code "58") (name "/THERM3") (class "Default")
      (node (ref "ADG725B") (pin "27") (pinfunction "S3B_27") (pintype "bidirectional"))
      (node (ref "MUSSEL3") (pin "P$3") (pinfunction "P$3_P$3") (pintype "bidirectional"))
      (node (ref "R36") (pin "1") (pinfunction "1_1") (pintype "passive"))
    )
    (net (code "59") (name "/THERM4") (class "Default")
      (node (ref "ADG725B") (pin "28") (pinfunction "S4B_28") (pintype "bidirectional"))
      (node (ref "MUSSEL4") (pin "P$3") (pinfunction "P$3_P$3") (pintype "bidirectional"))
      (node (ref "R37") (pin "1") (pinfunction "1_1") (pintype "passive"))
    )
    (net (code "60") (name "/THERM5") (class "Default")
      (node (ref "ADG725B") (pin "29") (pinfunction "S5B_29") (pintype "bidirectional"))
      (node (ref "MUSSEL5") (pin "P$3") (pinfunction "P$3_P$3") (pintype "bidirectional"))
      (node (ref "R38") (pin "1") (pinfunction "1_1") (pintype "passive"))
    )
    (net (code "61") (name "/THERM6") (class "Default")
      (node (ref "ADG725B") (pin "30") (pinfunction "S6B_30") (pintype "bidirectional"))
      (node (ref "MUSSEL6") (pin "P$3") (pinfunction "P$3_P$3") (pintype "bidirectional"))
      (node (ref "R39") (pin "1") (pinfunction "1_1") (pintype "passive"))
    )
    (net (code "62") (name "/THERM7") (class "Default")
      (node (ref "ADG725B") (pin "31") (pinfunction "S7B_31") (pintype "bidirectional"))
      (node (ref "MUSSEL7") (pin "P$3") (pinfunction "P$3_P$3") (pintype "bidirectional"))
      (node (ref "R40") (pin "1") (pinfunction "1_1") (pintype "passive"))
    )
    (net (code "63") (name "/THERM8") (class "Default")
      (node (ref "ADG725B") (pin "32") (pinfunction "S8B_32") (pintype "bidirectional"))
      (node (ref "MUSSEL8") (pin "P$3") (pinfunction "P$3_P$3") (pintype "bidirectional"))
      (node (ref "R41") (pin "1") (pinfunction "1_1") (pintype "passive"))
    )
    (net (code "64") (name "/THERM9") (class "Default")
      (node (ref "ADG725B") (pin "33") (pinfunction "S9B_33") (pintype "bidirectional"))
      (node (ref "MUSSEL9") (pin "P$3") (pinfunction "P$3_P$3") (pintype "bidirectional"))
      (node (ref "R42") (pin "1") (pinfunction "1_1") (pintype "passive"))
    )
    (net (code "65") (name "/THERM10") (class "Default")
      (node (ref "ADG725B") (pin "34") (pinfunction "S10B_34") (pintype "bidirectional"))
      (node (ref "MUSSEL10") (pin "P$3") (pinfunction "P$3_P$3") (pintype "bidirectional"))
      (node (ref "R43") (pin "1") (pinfunction "1_1") (pintype "passive"))
    )
    (net (code "66") (name "/THERM11") (class "Default")
      (node (ref "ADG725B") (pin "35") (pinfunction "S11B_35") (pintype "bidirectional"))
      (node (ref "MUSSEL11") (pin "P$3") (pinfunction "P$3_P$3") (pintype "bidirectional"))
      (node (ref "R44") (pin "1") (pinfunction "1_1") (pintype "passive"))
    )
    (net (code "67") (name "/THERM12") (class "Default")
      (node (ref "ADG725B") (pin "36") (pinfunction "S12B_36") (pintype "bidirectional"))
      (node (ref "MUSSEL12") (pin "P$3") (pinfunction "P$3_P$3") (pintype "bidirectional"))
      (node (ref "R45") (pin "1") (pinfunction "1_1") (pintype "passive"))
    )
    (net (code "68") (name "/THERM13") (class "Default")
      (node (ref "ADG725B") (pin "37") (pinfunction "S13B_37") (pintype "bidirectional"))
      (node (ref "MUSSEL13") (pin "P$3") (pinfunction "P$3_P$3") (pintype "bidirectional"))
      (node (ref "R46") (pin "1") (pinfunction "1_1") (pintype "passive"))
    )
    (net (code "69") (name "/THERM14") (class "Default")
      (node (ref "ADG725B") (pin "38") (pinfunction "S14B_38") (pintype "bidirectional"))
      (node (ref "MUSSEL14") (pin "P$3") (pinfunction "P$3_P$3") (pintype "bidirectional"))
      (node (ref "R47") (pin "1") (pinfunction "1_1") (pintype "passive"))
    )
    (net (code "70") (name "/THERM15") (class "Default")
      (node (ref "ADG725B") (pin "39") (pinfunction "S15B_39") (pintype "bidirectional"))
      (node (ref "MUSSEL15") (pin "P$3") (pinfunction "P$3_P$3") (pintype "bidirectional"))
      (node (ref "R48") (pin "1") (pinfunction "1_1") (pintype "passive"))
    )
    (net (code "71") (name "/THERM16") (class "Default")
      (node (ref "ADG725B") (pin "40") (pinfunction "S16B_40") (pintype "bidirectional"))
      (node (ref "MUSSEL16") (pin "P$3") (pinfunction "P$3_P$3") (pintype "bidirectional"))
      (node (ref "R49") (pin "1") (pinfunction "1_1") (pintype "passive"))
    )
    (net (code "72") (name "/TO_FTDI_RX") (class "Default")
      (node (ref "ATMEGA328P") (pin "31") (pinfunction "PD1(TXD)_31") (pintype "bidirectional"))
      (node (ref "FTDI") (pin "2") (pinfunction "2_2") (pintype "passive"))
    )
    (net (code "73") (name "/TO_FTDI_TX") (class "Default")
      (node (ref "ATMEGA328P") (pin "30") (pinfunction "PD0(RXD)_30") (pintype "bidirectional"))
      (node (ref "FTDI") (pin "3") (pinfunction "3_3") (pintype "passive"))
    )
    (net (code "74") (name "/VBAT") (class "Default")
      (node (ref "DS3231M") (pin "6") (pinfunction "P$6_VBAT_6") (pintype "bidirectional"))
      (node (ref "U$5") (pin "P$1") (pinfunction "VBAT_P$1") (pintype "power_in"))
      (node (ref "U$5") (pin "P$2") (pinfunction "VBAT_P$2") (pintype "power_in"))
    )
    (net (code "75") (name "/VRAW") (class "Default")
      (node (ref "AP2204_VREG") (pin "P$1") (pinfunction "VIN_P$1") (pintype "input"))
      (node (ref "C9") (pin "+") (pinfunction "+_+") (pintype "passive"))
      (node (ref "MOSFET-P") (pin "2") (pinfunction "S_2") (pintype "passive"))
      (node (ref "MUSSEL1") (pin "P$1") (pinfunction "P$1_P$1") (pintype "bidirectional"))
      (node (ref "MUSSEL10") (pin "P$1") (pinfunction "P$1_P$1") (pintype "bidirectional"))
      (node (ref "MUSSEL11") (pin "P$1") (pinfunction "P$1_P$1") (pintype "bidirectional"))
      (node (ref "MUSSEL12") (pin "P$1") (pinfunction "P$1_P$1") (pintype "bidirectional"))
      (node (ref "MUSSEL13") (pin "P$1") (pinfunction "P$1_P$1") (pintype "bidirectional"))
      (node (ref "MUSSEL14") (pin "P$1") (pinfunction "P$1_P$1") (pintype "bidirectional"))
      (node (ref "MUSSEL15") (pin "P$1") (pinfunction "P$1_P$1") (pintype "bidirectional"))
      (node (ref "MUSSEL16") (pin "P$1") (pinfunction "P$1_P$1") (pintype "bidirectional"))
      (node (ref "MUSSEL2") (pin "P$1") (pinfunction "P$1_P$1") (pintype "bidirectional"))
      (node (ref "MUSSEL3") (pin "P$1") (pinfunction "P$1_P$1") (pintype "bidirectional"))
      (node (ref "MUSSEL4") (pin "P$1") (pinfunction "P$1_P$1") (pintype "bidirectional"))
      (node (ref "MUSSEL5") (pin "P$1") (pinfunction "P$1_P$1") (pintype "bidirectional"))
      (node (ref "MUSSEL6") (pin "P$1") (pinfunction "P$1_P$1") (pintype "bidirectional"))
      (node (ref "MUSSEL7") (pin "P$1") (pinfunction "P$1_P$1") (pintype "bidirectional"))
      (node (ref "MUSSEL8") (pin "P$1") (pinfunction "P$1_P$1") (pintype "bidirectional"))
      (node (ref "MUSSEL9") (pin "P$1") (pinfunction "P$1_P$1") (pintype "bidirectional"))
      (node (ref "R16") (pin "1") (pinfunction "1_1") (pintype "passive"))
      (node (ref "U$7") (pin "P$3") (pinfunction "C_P$3") (pintype "passive"))
      (node (ref "U$8") (pin "P$3") (pinfunction "C_P$3") (pintype "passive"))
      (node (ref "VRAW_TEST") (pin "1") (pinfunction "1_1") (pintype "passive"))
    )
    (net (code "76") (name "GND") (class "Default")
      (node (ref "ADG725B") (pin "23") (pinfunction "GND_23") (pintype "bidirectional"))
      (node (ref "ADG725B") (pin "24") (pinfunction "VSS_24") (pintype "bidirectional"))
      (node (ref "AP2204_VREG") (pin "P$2") (pinfunction "GND_P$2") (pintype "passive"))
      (node (ref "ATMEGA328P") (pin "21") (pinfunction "AGND_21") (pintype "bidirectional"))
      (node (ref "ATMEGA328P") (pin "3") (pinfunction "GND_3") (pintype "bidirectional"))
      (node (ref "ATMEGA328P") (pin "5") (pinfunction "GND_5") (pintype "bidirectional"))
      (node (ref "BATT_INPUT1") (pin "P$2") (pinfunction "P$2_P$2") (pintype "bidirectional"))
      (node (ref "BATT_INPUT2") (pin "P$2") (pinfunction "P$2_P$2") (pintype "bidirectional"))
      (node (ref "BJT_NPN") (pin "2") (pinfunction "E_2") (pintype "passive"))
      (node (ref "BUTTON1") (pin "P$1") (pinfunction "P_P$1") (pintype "passive"))
      (node (ref "BUTTON1") (pin "P$2") (pinfunction "P_P$2") (pintype "passive"))
      (node (ref "C1") (pin "2") (pinfunction "2_2") (pintype "passive"))
      (node (ref "C10") (pin "1") (pinfunction "1_1") (pintype "passive"))
      (node (ref "C11") (pin "2") (pinfunction "2_2") (pintype "passive"))
      (node (ref "C12") (pin "2") (pinfunction "2_2") (pintype "passive"))
      (node (ref "C13") (pin "2") (pinfunction "2_2") (pintype "passive"))
      (node (ref "C14") (pin "2") (pinfunction "2_2") (pintype "passive"))
      (node (ref "C3") (pin "2") (pinfunction "2_2") (pintype "passive"))
      (node (ref "C4") (pin "2") (pinfunction "2_2") (pintype "passive"))
      (node (ref "C5") (pin "2") (pinfunction "2_2") (pintype "passive"))
      (node (ref "C6") (pin "2") (pinfunction "2_2") (pintype "passive"))
      (node (ref "C7") (pin "-") (pinfunction "-_-") (pintype "passive"))
      (node (ref "C8") (pin "2") (pinfunction "2_2") (pintype "passive"))
      (node (ref "C9") (pin "-") (pinfunction "-_-") (pintype "passive"))
      (node (ref "DS3231M") (pin "5") (pinfunction "P$5_GND_5") (pintype "power_in"))
      (node (ref "FTDI") (pin "5") (pinfunction "5_5") (pintype "passive"))
      (node (ref "FTDI") (pin "6") (pinfunction "6_6") (pintype "passive"))
      (node (ref "ISP") (pin "6") (pinfunction "6_6") (pintype "passive"))
      (node (ref "MAX6103") (pin "3") (pinfunction "GND_3") (pintype "bidirectional"))
      (node (ref "MUSSEL1") (pin "P$2") (pinfunction "P$2_P$2") (pintype "bidirectional"))
      (node (ref "MUSSEL10") (pin "P$2") (pinfunction "P$2_P$2") (pintype "bidirectional"))
      (node (ref "MUSSEL11") (pin "P$2") (pinfunction "P$2_P$2") (pintype "bidirectional"))
      (node (ref "MUSSEL12") (pin "P$2") (pinfunction "P$2_P$2") (pintype "bidirectional"))
      (node (ref "MUSSEL13") (pin "P$2") (pinfunction "P$2_P$2") (pintype "bidirectional"))
      (node (ref "MUSSEL14") (pin "P$2") (pinfunction "P$2_P$2") (pintype "bidirectional"))
      (node (ref "MUSSEL15") (pin "P$2") (pinfunction "P$2_P$2") (pintype "bidirectional"))
      (node (ref "MUSSEL16") (pin "P$2") (pinfunction "P$2_P$2") (pintype "bidirectional"))
      (node (ref "MUSSEL2") (pin "P$2") (pinfunction "P$2_P$2") (pintype "bidirectional"))
      (node (ref "MUSSEL3") (pin "P$2") (pinfunction "P$2_P$2") (pintype "bidirectional"))
      (node (ref "MUSSEL4") (pin "P$2") (pinfunction "P$2_P$2") (pintype "bidirectional"))
      (node (ref "MUSSEL5") (pin "P$2") (pinfunction "P$2_P$2") (pintype "bidirectional"))
      (node (ref "MUSSEL6") (pin "P$2") (pinfunction "P$2_P$2") (pintype "bidirectional"))
      (node (ref "MUSSEL7") (pin "P$2") (pinfunction "P$2_P$2") (pintype "bidirectional"))
      (node (ref "MUSSEL8") (pin "P$2") (pinfunction "P$2_P$2") (pintype "bidirectional"))
      (node (ref "MUSSEL9") (pin "P$2") (pinfunction "P$2_P$2") (pintype "bidirectional"))
      (node (ref "OLED") (pin "GND") (pinfunction "GND_GND") (pintype "bidirectional"))
      (node (ref "PCA9685") (pin "1") (pinfunction "A0_1") (pintype "bidirectional"))
      (node (ref "PCA9685") (pin "14") (pinfunction "GND_14") (pintype "power_in"))
      (node (ref "PCA9685") (pin "2") (pinfunction "A1_2") (pintype "bidirectional"))
      (node (ref "PCA9685") (pin "24") (pinfunction "A5_24") (pintype "bidirectional"))
      (node (ref "PCA9685") (pin "25") (pinfunction "EXTCLK_25") (pintype "input"))
      (node (ref "PCA9685") (pin "3") (pinfunction "A2_3") (pintype "bidirectional"))
      (node (ref "PCA9685") (pin "4") (pinfunction "A3_4") (pintype "bidirectional"))
      (node (ref "PCA9685") (pin "5") (pinfunction "A4_5") (pintype "bidirectional"))
      (node (ref "R14") (pin "2") (pinfunction "2_2") (pintype "passive"))
      (node (ref "R15") (pin "2") (pinfunction "2_2") (pintype "passive"))
      (node (ref "R18") (pin "2") (pinfunction "2_2") (pintype "passive"))
      (node (ref "R19") (pin "2") (pinfunction "2_2") (pintype "passive"))
      (node (ref "R20") (pin "2") (pinfunction "2_2") (pintype "passive"))
      (node (ref "R21") (pin "2") (pinfunction "2_2") (pintype "passive"))
      (node (ref "R22") (pin "2") (pinfunction "2_2") (pintype "passive"))
      (node (ref "R23") (pin "2") (pinfunction "2_2") (pintype "passive"))
      (node (ref "R24") (pin "2") (pinfunction "2_2") (pintype "passive"))
      (node (ref "R25") (pin "2") (pinfunction "2_2") (pintype "passive"))
      (node (ref "R26") (pin "2") (pinfunction "2_2") (pintype "passive"))
      (node (ref "R27") (pin "2") (pinfunction "2_2") (pintype "passive"))
      (node (ref "R28") (pin "2") (pinfunction "2_2") (pintype "passive"))
      (node (ref "R29") (pin "2") (pinfunction "2_2") (pintype "passive"))
      (node (ref "R30") (pin "2") (pinfunction "2_2") (pintype "passive"))
      (node (ref "R31") (pin "2") (pinfunction "2_2") (pintype "passive"))
      (node (ref "R32") (pin "2") (pinfunction "2_2") (pintype "passive"))
      (node (ref "R33") (pin "2") (pinfunction "2_2") (pintype "passive"))
      (node (ref "RESET") (pin "P$1") (pinfunction "P_P$1") (pintype "passive"))
      (node (ref "RESET") (pin "P$2") (pinfunction "P_P$2") (pintype "passive"))
      (node (ref "TC2030_ISP") (pin "6") (pinfunction "GND_6") (pintype "power_in"))
      (node (ref "TEMP17") (pin "P$2") (pinfunction "P$2_P$2") (pintype "bidirectional"))
      (node (ref "TEMP18") (pin "P$2") (pinfunction "P$2_P$2") (pintype "bidirectional"))
      (node (ref "TEMP19") (pin "P$2") (pinfunction "P$2_P$2") (pintype "bidirectional"))
      (node (ref "TEMP20") (pin "P$2") (pinfunction "P$2_P$2") (pintype "bidirectional"))
      (node (ref "U$10") (pin "1") (pinfunction "S_1") (pintype "bidirectional"))
      (node (ref "U$10") (pin "2") (pinfunction "S_2") (pintype "bidirectional"))
      (node (ref "U$10") (pin "3") (pinfunction "S_3") (pintype "bidirectional"))
      (node (ref "U$11") (pin "1") (pinfunction "S_1") (pintype "bidirectional"))
      (node (ref "U$11") (pin "2") (pinfunction "S_2") (pintype "bidirectional"))
      (node (ref "U$11") (pin "3") (pinfunction "S_3") (pintype "bidirectional"))
      (node (ref "U$12") (pin "1") (pinfunction "S_1") (pintype "bidirectional"))
      (node (ref "U$12") (pin "2") (pinfunction "S_2") (pintype "bidirectional"))
      (node (ref "U$12") (pin "3") (pinfunction "S_3") (pintype "bidirectional"))
      (node (ref "U$13") (pin "1") (pinfunction "S_1") (pintype "bidirectional"))
      (node (ref "U$13") (pin "2") (pinfunction "S_2") (pintype "bidirectional"))
      (node (ref "U$13") (pin "3") (pinfunction "S_3") (pintype "bidirectional"))
      (node (ref "U$14") (pin "1") (pinfunction "S_1") (pintype "bidirectional"))
      (node (ref "U$14") (pin "2") (pinfunction "S_2") (pintype "bidirectional"))
      (node (ref "U$14") (pin "3") (pinfunction "S_3") (pintype "bidirectional"))
      (node (ref "U$15") (pin "1") (pinfunction "S_1") (pintype "bidirectional"))
      (node (ref "U$15") (pin "2") (pinfunction "S_2") (pintype "bidirectional"))
      (node (ref "U$15") (pin "3") (pinfunction "S_3") (pintype "bidirectional"))
      (node (ref "U$16") (pin "1") (pinfunction "S_1") (pintype "bidirectional"))
      (node (ref "U$16") (pin "2") (pinfunction "S_2") (pintype "bidirectional"))
      (node (ref "U$16") (pin "3") (pinfunction "S_3") (pintype "bidirectional"))
      (node (ref "U$17") (pin "1") (pinfunction "S_1") (pintype "bidirectional"))
      (node (ref "U$17") (pin "2") (pinfunction "S_2") (pintype "bidirectional"))
      (node (ref "U$17") (pin "3") (pinfunction "S_3") (pintype "bidirectional"))
      (node (ref "U$18") (pin "1") (pinfunction "S_1") (pintype "bidirectional"))
      (node (ref "U$18") (pin "2") (pinfunction "S_2") (pintype "bidirectional"))
      (node (ref "U$18") (pin "3") (pinfunction "S_3") (pintype "bidirectional"))
      (node (ref "U$19") (pin "1") (pinfunction "S_1") (pintype "bidirectional"))
      (node (ref "U$19") (pin "2") (pinfunction "S_2") (pintype "bidirectional"))
      (node (ref "U$19") (pin "3") (pinfunction "S_3") (pintype "bidirectional"))
      (node (ref "U$2") (pin "GND6") (pinfunction "VSS_GND_GND6") (pintype "power_in"))
      (node (ref "U$2") (pin "MNT1") (pinfunction "GND1_MNT1") (pintype "power_in"))
      (node (ref "U$2") (pin "MNT2") (pinfunction "GND2_MNT2") (pintype "power_in"))
      (node (ref "U$2") (pin "MNT3") (pinfunction "GND3_MNT3") (pintype "power_in"))
      (node (ref "U$2") (pin "MNT4") (pinfunction "GND4_MNT4") (pintype "power_in"))
      (node (ref "U$20") (pin "1") (pinfunction "S_1") (pintype "bidirectional"))
      (node (ref "U$20") (pin "2") (pinfunction "S_2") (pintype "bidirectional"))
      (node (ref "U$20") (pin "3") (pinfunction "S_3") (pintype "bidirectional"))
      (node (ref "U$21") (pin "1") (pinfunction "S_1") (pintype "bidirectional"))
      (node (ref "U$21") (pin "2") (pinfunction "S_2") (pintype "bidirectional"))
      (node (ref "U$21") (pin "3") (pinfunction "S_3") (pintype "bidirectional"))
      (node (ref "U$22") (pin "1") (pinfunction "S_1") (pintype "bidirectional"))
      (node (ref "U$22") (pin "2") (pinfunction "S_2") (pintype "bidirectional"))
      (node (ref "U$22") (pin "3") (pinfunction "S_3") (pintype "bidirectional"))
      (node (ref "U$23") (pin "1") (pinfunction "S_1") (pintype "bidirectional"))
      (node (ref "U$23") (pin "2") (pinfunction "S_2") (pintype "bidirectional"))
      (node (ref "U$23") (pin "3") (pinfunction "S_3") (pintype "bidirectional"))
      (node (ref "U$24") (pin "1") (pinfunction "S_1") (pintype "bidirectional"))
      (node (ref "U$24") (pin "2") (pinfunction "S_2") (pintype "bidirectional"))
      (node (ref "U$24") (pin "3") (pinfunction "S_3") (pintype "bidirectional"))
      (node (ref "U$25") (pin "1") (pinfunction "S_1") (pintype "bidirectional"))
      (node (ref "U$25") (pin "2") (pinfunction "S_2") (pintype "bidirectional"))
      (node (ref "U$25") (pin "3") (pinfunction "S_3") (pintype "bidirectional"))
      (node (ref "U$5") (pin "GND") (pinfunction "GND_GND") (pintype "power_in"))
      (node (ref "VRAW_TEST") (pin "2") (pinfunction "2_2") (pintype "passive"))
    )
    (net (code "77") (name "Net-(ADG725B-S1A)") (class "Default")
      (node (ref "ADG725B") (pin "12") (pinfunction "S1A_12") (pintype "bidirectional"))
      (node (ref "R34") (pin "2") (pinfunction "2_2") (pintype "passive"))
    )
    (net (code "78") (name "Net-(ADG725B-S2A)") (class "Default")
      (node (ref "ADG725B") (pin "11") (pinfunction "S2A_11") (pintype "bidirectional"))
      (node (ref "R35") (pin "2") (pinfunction "2_2") (pintype "passive"))
    )
    (net (code "79") (name "Net-(ADG725B-S3A)") (class "Default")
      (node (ref "ADG725B") (pin "10") (pinfunction "S3A_10") (pintype "bidirectional"))
      (node (ref "R36") (pin "2") (pinfunction "2_2") (pintype "passive"))
    )
    (net (code "80") (name "Net-(ADG725B-S4A)") (class "Default")
      (node (ref "ADG725B") (pin "9") (pinfunction "S4A_9") (pintype "bidirectional"))
      (node (ref "R37") (pin "2") (pinfunction "2_2") (pintype "passive"))
    )
    (net (code "81") (name "Net-(ADG725B-S5A)") (class "Default")
      (node (ref "ADG725B") (pin "8") (pinfunction "S5A_8") (pintype "bidirectional"))
      (node (ref "R38") (pin "2") (pinfunction "2_2") (pintype "passive"))
    )
    (net (code "82") (name "Net-(ADG725B-S6A)") (class "Default")
      (node (ref "ADG725B") (pin "7") (pinfunction "S6A_7") (pintype "bidirectional"))
      (node (ref "R39") (pin "2") (pinfunction "2_2") (pintype "passive"))
    )
    (net (code "83") (name "Net-(ADG725B-S7A)") (class "Default")
      (node (ref "ADG725B") (pin "6") (pinfunction "S7A_6") (pintype "bidirectional"))
      (node (ref "R40") (pin "2") (pinfunction "2_2") (pintype "passive"))
    )
    (net (code "84") (name "Net-(ADG725B-S8A)") (class "Default")
      (node (ref "ADG725B") (pin "5") (pinfunction "S8A_5") (pintype "bidirectional"))
      (node (ref "R41") (pin "2") (pinfunction "2_2") (pintype "passive"))
    )
    (net (code "85") (name "Net-(ADG725B-S9A)") (class "Default")
      (node (ref "ADG725B") (pin "4") (pinfunction "S9A_4") (pintype "bidirectional"))
      (node (ref "R42") (pin "2") (pinfunction "2_2") (pintype "passive"))
    )
    (net (code "86") (name "Net-(ADG725B-S10A)") (class "Default")
      (node (ref "ADG725B") (pin "3") (pinfunction "S10A_3") (pintype "bidirectional"))
      (node (ref "R43") (pin "2") (pinfunction "2_2") (pintype "passive"))
    )
    (net (code "87") (name "Net-(ADG725B-S11A)") (class "Default")
      (node (ref "ADG725B") (pin "2") (pinfunction "S11A_2") (pintype "bidirectional"))
      (node (ref "R44") (pin "2") (pinfunction "2_2") (pintype "passive"))
    )
    (net (code "88") (name "Net-(ADG725B-S12A)") (class "Default")
      (node (ref "ADG725B") (pin "1") (pinfunction "S12A_1") (pintype "bidirectional"))
      (node (ref "R45") (pin "2") (pinfunction "2_2") (pintype "passive"))
    )
    (net (code "89") (name "Net-(ADG725B-S13A)") (class "Default")
      (node (ref "ADG725B") (pin "48") (pinfunction "S13A_48") (pintype "bidirectional"))
      (node (ref "R46") (pin "2") (pinfunction "2_2") (pintype "passive"))
    )
    (net (code "90") (name "Net-(ADG725B-S14A)") (class "Default")
      (node (ref "ADG725B") (pin "47") (pinfunction "S14A_47") (pintype "bidirectional"))
      (node (ref "R47") (pin "2") (pinfunction "2_2") (pintype "passive"))
    )
    (net (code "91") (name "Net-(ADG725B-S15A)") (class "Default")
      (node (ref "ADG725B") (pin "46") (pinfunction "S15A_46") (pintype "bidirectional"))
      (node (ref "R48") (pin "2") (pinfunction "2_2") (pintype "passive"))
    )
    (net (code "92") (name "Net-(ADG725B-S16A)") (class "Default")
      (node (ref "ADG725B") (pin "45") (pinfunction "S16A_45") (pintype "bidirectional"))
      (node (ref "R49") (pin "2") (pinfunction "2_2") (pintype "passive"))
    )
    (net (code "93") (name "Net-(BATT_INPUT1-PadP$1)") (class "Default")
      (node (ref "BATT_INPUT1") (pin "P$1") (pinfunction "P$1_P$1") (pintype "bidirectional"))
      (node (ref "U$7") (pin "P$1") (pinfunction "A_P$1") (pintype "passive"))
      (node (ref "U$7") (pin "P$2") (pinfunction "A_P$2") (pintype "passive"))
    )
    (net (code "94") (name "Net-(BATT_INPUT2-PadP$1)") (class "Default")
      (node (ref "BATT_INPUT2") (pin "P$1") (pinfunction "P$1_P$1") (pintype "bidirectional"))
      (node (ref "U$8") (pin "P$1") (pinfunction "A_P$1") (pintype "passive"))
      (node (ref "U$8") (pin "P$2") (pinfunction "A_P$2") (pintype "passive"))
    )
    (net (code "95") (name "Net-(BJT_NPN-B)") (class "Default")
      (node (ref "BJT_NPN") (pin "1") (pinfunction "B_1") (pintype "passive"))
      (node (ref "R9") (pin "1") (pinfunction "1_1") (pintype "passive"))
    )
    (net (code "96") (name "Net-(BJT_NPN-C)") (class "Default")
      (node (ref "BJT_NPN") (pin "3") (pinfunction "C_3") (pintype "passive"))
      (node (ref "MOSFET-P") (pin "1") (pinfunction "G_1") (pintype "passive"))
      (node (ref "R16") (pin "2") (pinfunction "2_2") (pintype "passive"))
    )
    (net (code "97") (name "Net-(MOSFET-P-D)") (class "Default")
      (node (ref "MOSFET-P") (pin "3") (pinfunction "D_3") (pintype "passive"))
      (node (ref "R13") (pin "1") (pinfunction "1_1") (pintype "passive"))
    )
    (net (code "98") (name "Net-(R10-Pad1)") (class "Default")
      (node (ref "R10") (pin "1") (pinfunction "1_1") (pintype "passive"))
      (node (ref "RGB_LED") (pin "P$3") (pinfunction "P$3_P$3") (pintype "bidirectional"))
    )
    (net (code "99") (name "Net-(R11-Pad1)") (class "Default")
      (node (ref "R11") (pin "1") (pinfunction "1_1") (pintype "passive"))
      (node (ref "RGB_LED") (pin "P$4") (pinfunction "P$4_P$4") (pintype "bidirectional"))
    )
    (net (code "100") (name "Net-(R12-Pad1)") (class "Default")
      (node (ref "R12") (pin "1") (pinfunction "1_1") (pintype "passive"))
      (node (ref "RGB_LED") (pin "P$2") (pinfunction "P$2_P$2") (pintype "bidirectional"))
    )
    (net (code "101") (name "Net-(U$2-DAT1_NC)") (class "Default")
      (node (ref "R7") (pin "1") (pinfunction "1_1") (pintype "passive"))
      (node (ref "U$2") (pin "NC1") (pinfunction "DAT1_NC_NC1") (pintype "bidirectional"))
    )
    (net (code "102") (name "Net-(U$2-DAT2_RES)") (class "Default")
      (node (ref "R6") (pin "1") (pinfunction "1_1") (pintype "passive"))
      (node (ref "U$2") (pin "RES8") (pinfunction "DAT2_RES_RES8") (pintype "bidirectional"))
    )
    (net (code "103") (name "VCC") (class "Default")
      (node (ref "ADG725B") (pin "13") (pinfunction "VDD_13") (pintype "bidirectional"))
      (node (ref "ADG725B") (pin "14") (pinfunction "VDD_14") (pintype "bidirectional"))
      (node (ref "AP2204_VREG") (pin "P$3") (pinfunction "VOUT_P$3") (pintype "output"))
      (node (ref "ATMEGA328P") (pin "4") (pinfunction "VCC_4") (pintype "bidirectional"))
      (node (ref "ATMEGA328P") (pin "6") (pinfunction "VCC_6") (pintype "bidirectional"))
      (node (ref "C1") (pin "1") (pinfunction "1_1") (pintype "passive"))
      (node (ref "C11") (pin "1") (pinfunction "1_1") (pintype "passive"))
      (node (ref "C12") (pin "1") (pinfunction "1_1") (pintype "passive"))
      (node (ref "C4") (pin "1") (pinfunction "1_1") (pintype "passive"))
      (node (ref "C5") (pin "1") (pinfunction "1_1") (pintype "passive"))
      (node (ref "C6") (pin "1") (pinfunction "1_1") (pintype "passive"))
      (node (ref "C7") (pin "+") (pinfunction "+_+") (pintype "passive"))
      (node (ref "C8") (pin "1") (pinfunction "1_1") (pintype "passive"))
      (node (ref "DS3231M") (pin "2") (pinfunction "P$2_VCC_2") (pintype "power_in"))
      (node (ref "FTDI") (pin "4") (pinfunction "4_4") (pintype "passive"))
      (node (ref "INDUCTOR") (pin "P$2") (pinfunction "2_P$2") (pintype "passive"))
      (node (ref "ISP") (pin "2") (pinfunction "2_2") (pintype "passive"))
      (node (ref "MAX6103") (pin "1") (pinfunction "VIN_1") (pintype "bidirectional"))
      (node (ref "OLED") (pin "VCC") (pinfunction "VCC_VCC") (pintype "bidirectional"))
      (node (ref "PCA9685") (pin "28") (pinfunction "VDD_28") (pintype "power_in"))
      (node (ref "R2") (pin "2") (pinfunction "2_2") (pintype "passive"))
      (node (ref "R3") (pin "2") (pinfunction "2_2") (pintype "passive"))
      (node (ref "R4") (pin "2") (pinfunction "2_2") (pintype "passive"))
      (node (ref "R5") (pin "2") (pinfunction "2_2") (pintype "passive"))
      (node (ref "R6") (pin "2") (pinfunction "2_2") (pintype "passive"))
      (node (ref "R7") (pin "2") (pinfunction "2_2") (pintype "passive"))
      (node (ref "R8") (pin "2") (pinfunction "2_2") (pintype "passive"))
      (node (ref "RGB_LED") (pin "P$1") (pinfunction "P$1_ANODE_P$1") (pintype "bidirectional"))
      (node (ref "TC2030_ISP") (pin "2") (pinfunction "VCC_2") (pintype "power_in"))
      (node (ref "TEMP17") (pin "P$4") (pinfunction "P$4_P$4") (pintype "bidirectional"))
      (node (ref "TEMP18") (pin "P$4") (pinfunction "P$4_P$4") (pintype "bidirectional"))
      (node (ref "TEMP19") (pin "P$4") (pinfunction "P$4_P$4") (pintype "bidirectional"))
      (node (ref "TEMP20") (pin "P$4") (pinfunction "P$4_P$4") (pintype "bidirectional"))
      (node (ref "U$2") (pin "VDD4") (pinfunction "VDD_VDD4") (pintype "power_in"))
    )
    (net (code "104") (name "unconnected-(ATMEGA328P-ADC6-Pad19)") (class "Default")
      (node (ref "ATMEGA328P") (pin "19") (pinfunction "ADC6_19") (pintype "bidirectional"))
    )
    (net (code "105") (name "unconnected-(ATMEGA328P-PB7(XTAL2{slash}TOSC2)-Pad8)") (class "Default")
      (node (ref "ATMEGA328P") (pin "8") (pinfunction "PB7(XTAL2/TOSC2)_8") (pintype "bidirectional"))
    )
    (net (code "106") (name "unconnected-(ATMEGA328P-PC3(ADC3)-Pad26)") (class "Default")
      (node (ref "ATMEGA328P") (pin "26") (pinfunction "PC3(ADC3)_26") (pintype "bidirectional"))
    )
    (net (code "107") (name "unconnected-(DS3231M-P$3_INT-Pad3)") (class "Default")
      (node (ref "DS3231M") (pin "3") (pinfunction "P$3_INT_3") (pintype "bidirectional"))
    )
    (net (code "108") (name "unconnected-(DS3231M-P$4_RST-Pad4)") (class "Default")
      (node (ref "DS3231M") (pin "4") (pinfunction "P$4_RST_4") (pintype "bidirectional"))
    )
    (net (code "109") (name "unconnected-(TEMP17-PadP$3)") (class "Default")
      (node (ref "TEMP17") (pin "P$3") (pinfunction "P$3_P$3") (pintype "bidirectional"))
    )
    (net (code "110") (name "unconnected-(TEMP18-PadP$3)") (class "Default")
      (node (ref "TEMP18") (pin "P$3") (pinfunction "P$3_P$3") (pintype "bidirectional"))
    )
    (net (code "111") (name "unconnected-(TEMP19-PadP$3)") (class "Default")
      (node (ref "TEMP19") (pin "P$3") (pinfunction "P$3_P$3") (pintype "bidirectional"))
    )
    (net (code "112") (name "unconnected-(TEMP20-PadP$3)") (class "Default")
      (node (ref "TEMP20") (pin "P$3") (pinfunction "P$3_P$3") (pintype "bidirectional"))
    )
    (net (code "113") (name "unconnected-(U$2-CARD_DETECT-PadCARD_DETECT1)") (class "Default")
      (node (ref "U$2") (pin "CARD_DETECT1") (pinfunction "CARD_DETECT_CARD_DETECT1") (pintype "passive"))
    )
    (net (code "114") (name "unconnected-(U$2-CARD_DETECT1-PadCARD_DETECT2)") (class "Default")
      (node (ref "U$2") (pin "CARD_DETECT2") (pinfunction "CARD_DETECT1_CARD_DETECT2") (pintype "passive"))
    )
  )
)
